# Display.net
KiCad netlist of a schematic drawn in EAGLE
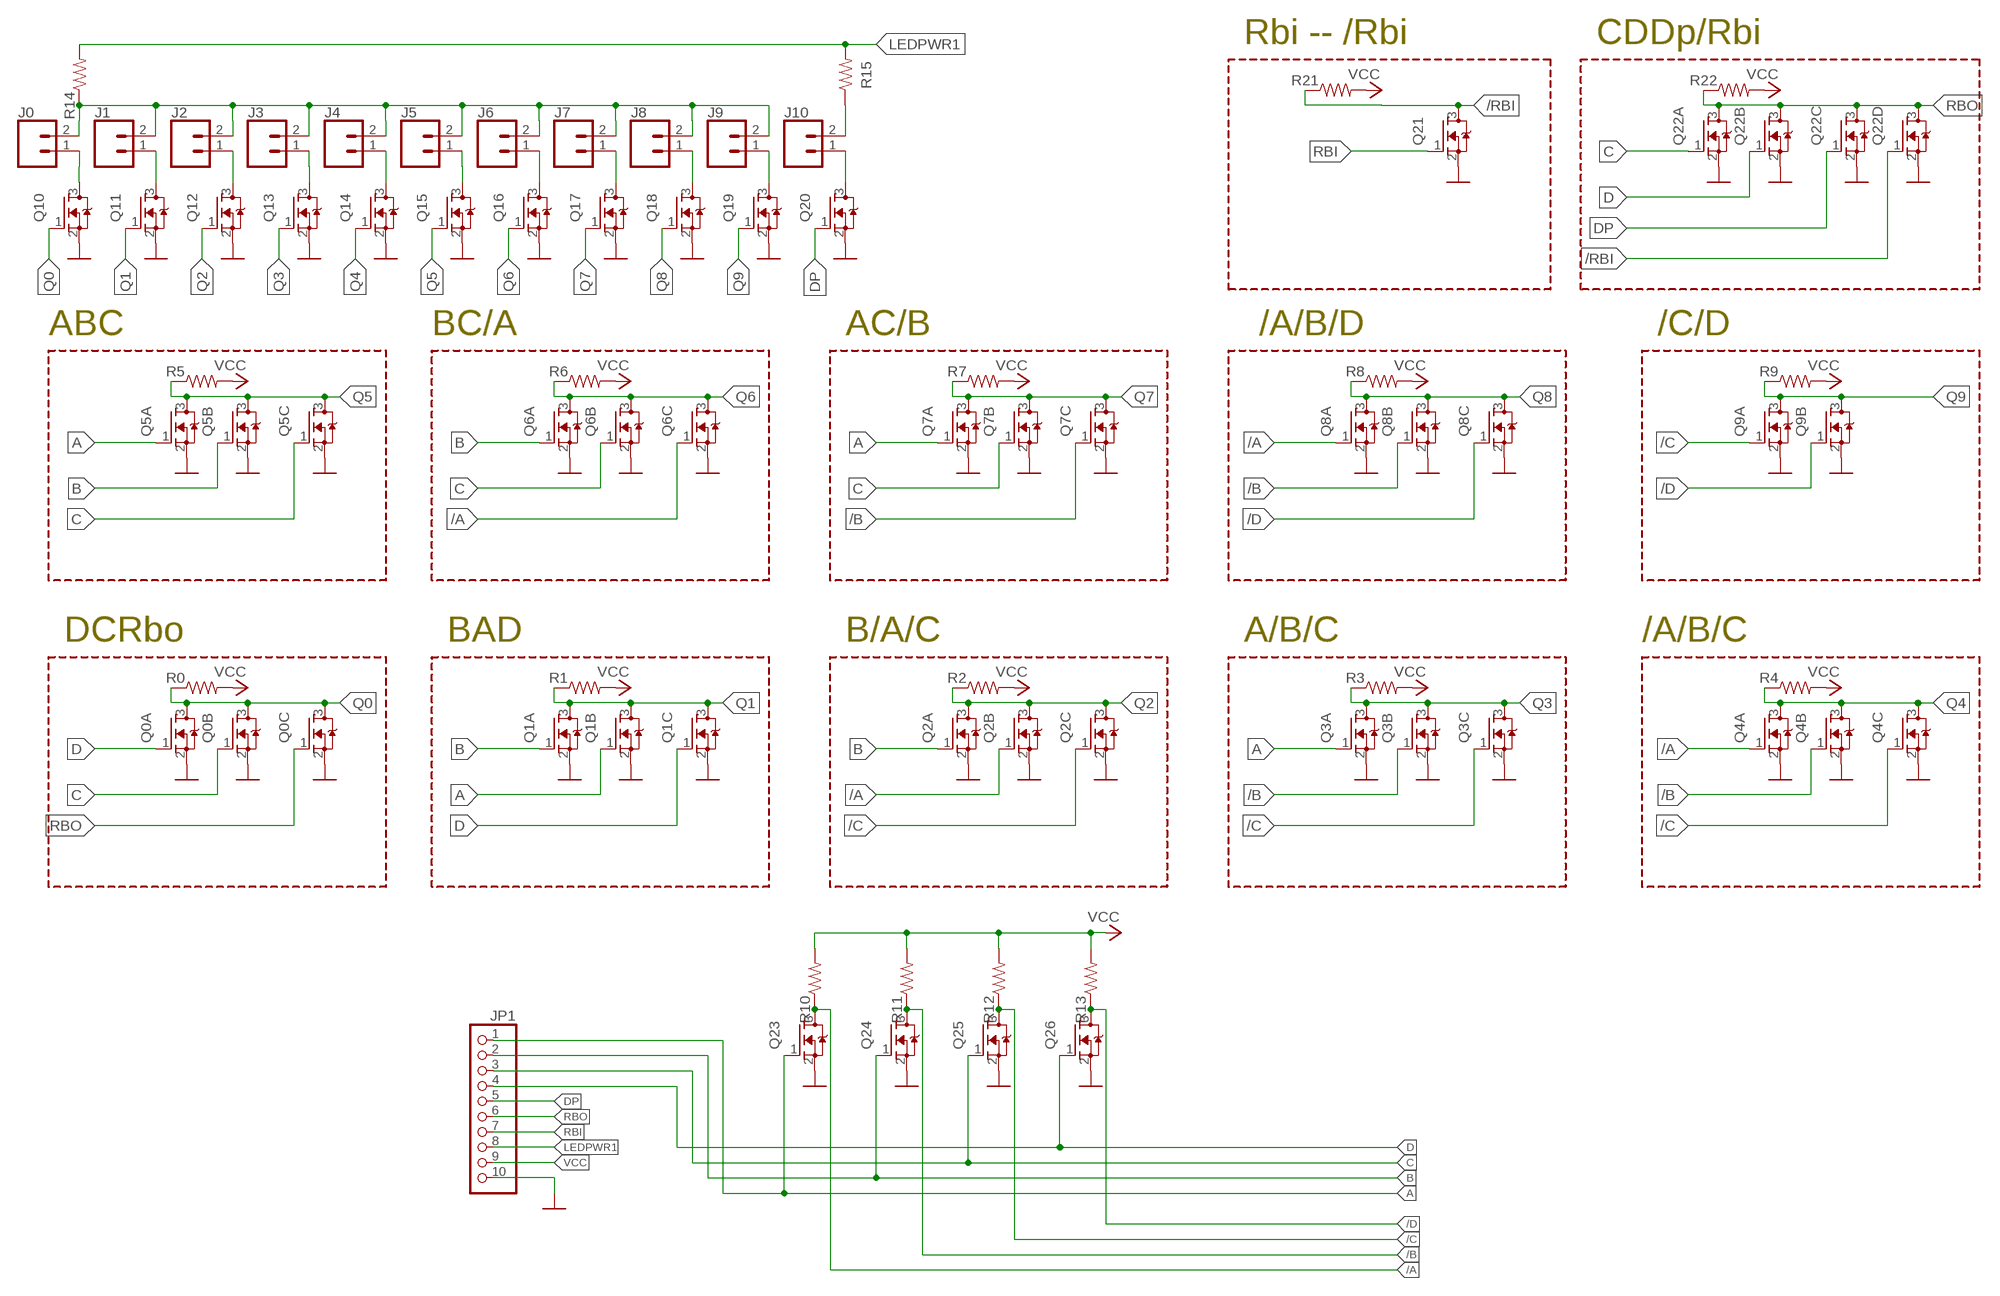
[diagram p0: schematic, sheet 1]

(export (version "E")
  (design (tool "Eeschema 10.0.6"))
  (components
    (comp (ref "J0")
      (value "CONN_02")
      (footprint "eagle-import:1X02")
      (libsource (lib "eagle-import") (part "CONN_02"))
    )
    (comp (ref "J1")
      (value "CONN_02")
      (footprint "eagle-import:1X02")
      (libsource (lib "eagle-import") (part "CONN_02"))
    )
    (comp (ref "J2")
      (value "CONN_02")
      (footprint "eagle-import:1X02")
      (libsource (lib "eagle-import") (part "CONN_02"))
    )
    (comp (ref "J3")
      (value "CONN_02")
      (footprint "eagle-import:1X02")
      (libsource (lib "eagle-import") (part "CONN_02"))
    )
    (comp (ref "J4")
      (value "CONN_02")
      (footprint "eagle-import:1X02")
      (libsource (lib "eagle-import") (part "CONN_02"))
    )
    (comp (ref "J5")
      (value "CONN_02")
      (footprint "eagle-import:1X02")
      (libsource (lib "eagle-import") (part "CONN_02"))
    )
    (comp (ref "J6")
      (value "CONN_02")
      (footprint "eagle-import:1X02")
      (libsource (lib "eagle-import") (part "CONN_02"))
    )
    (comp (ref "J7")
      (value "CONN_02")
      (footprint "eagle-import:1X02")
      (libsource (lib "eagle-import") (part "CONN_02"))
    )
    (comp (ref "J8")
      (value "CONN_02")
      (footprint "eagle-import:1X02")
      (libsource (lib "eagle-import") (part "CONN_02"))
    )
    (comp (ref "J9")
      (value "CONN_02")
      (footprint "eagle-import:1X02")
      (libsource (lib "eagle-import") (part "CONN_02"))
    )
    (comp (ref "J10")
      (value "CONN_02")
      (footprint "eagle-import:1X02")
      (libsource (lib "eagle-import") (part "CONN_02"))
    )
    (comp (ref "JP1")
      (value "PINHD-1X10/90")
      (footprint "eagle-import:1X10_90")
      (libsource (lib "eagle-import") (part "PINHD-1X10/90"))
    )
    (comp (ref "Q0A")
      (value "310mA/60V/1.6Ω")
      (footprint "eagle-import:SOT23")
      (libsource (lib "eagle-import") (part "NMOSREFLOW"))
    )
    (comp (ref "Q0B")
      (value "310mA/60V/1.6Ω")
      (footprint "eagle-import:SOT23")
      (libsource (lib "eagle-import") (part "NMOSREFLOW"))
    )
    (comp (ref "Q0C")
      (value "310mA/60V/1.6Ω")
      (footprint "eagle-import:SOT23")
      (libsource (lib "eagle-import") (part "NMOSREFLOW"))
    )
    (comp (ref "Q1A")
      (value "310mA/60V/1.6Ω")
      (footprint "eagle-import:SOT23")
      (libsource (lib "eagle-import") (part "NMOSREFLOW"))
    )
    (comp (ref "Q1B")
      (value "310mA/60V/1.6Ω")
      (footprint "eagle-import:SOT23")
      (libsource (lib "eagle-import") (part "NMOSREFLOW"))
    )
    (comp (ref "Q1C")
      (value "310mA/60V/1.6Ω")
      (footprint "eagle-import:SOT23")
      (libsource (lib "eagle-import") (part "NMOSREFLOW"))
    )
    (comp (ref "Q2A")
      (value "310mA/60V/1.6Ω")
      (footprint "eagle-import:SOT23")
      (libsource (lib "eagle-import") (part "NMOSREFLOW"))
    )
    (comp (ref "Q2B")
      (value "310mA/60V/1.6Ω")
      (footprint "eagle-import:SOT23")
      (libsource (lib "eagle-import") (part "NMOSREFLOW"))
    )
    (comp (ref "Q2C")
      (value "310mA/60V/1.6Ω")
      (footprint "eagle-import:SOT23")
      (libsource (lib "eagle-import") (part "NMOSREFLOW"))
    )
    (comp (ref "Q3A")
      (value "310mA/60V/1.6Ω")
      (footprint "eagle-import:SOT23")
      (libsource (lib "eagle-import") (part "NMOSREFLOW"))
    )
    (comp (ref "Q3B")
      (value "310mA/60V/1.6Ω")
      (footprint "eagle-import:SOT23")
      (libsource (lib "eagle-import") (part "NMOSREFLOW"))
    )
    (comp (ref "Q3C")
      (value "310mA/60V/1.6Ω")
      (footprint "eagle-import:SOT23")
      (libsource (lib "eagle-import") (part "NMOSREFLOW"))
    )
    (comp (ref "Q4A")
      (value "310mA/60V/1.6Ω")
      (footprint "eagle-import:SOT23")
      (libsource (lib "eagle-import") (part "NMOSREFLOW"))
    )
    (comp (ref "Q4B")
      (value "310mA/60V/1.6Ω")
      (footprint "eagle-import:SOT23")
      (libsource (lib "eagle-import") (part "NMOSREFLOW"))
    )
    (comp (ref "Q4C")
      (value "310mA/60V/1.6Ω")
      (footprint "eagle-import:SOT23")
      (libsource (lib "eagle-import") (part "NMOSREFLOW"))
    )
    (comp (ref "Q5A")
      (value "310mA/60V/1.6Ω")
      (footprint "eagle-import:SOT23")
      (libsource (lib "eagle-import") (part "NMOSREFLOW"))
    )
    (comp (ref "Q5B")
      (value "310mA/60V/1.6Ω")
      (footprint "eagle-import:SOT23")
      (libsource (lib "eagle-import") (part "NMOSREFLOW"))
    )
    (comp (ref "Q5C")
      (value "310mA/60V/1.6Ω")
      (footprint "eagle-import:SOT23")
      (libsource (lib "eagle-import") (part "NMOSREFLOW"))
    )
    (comp (ref "Q6A")
      (value "310mA/60V/1.6Ω")
      (footprint "eagle-import:SOT23")
      (libsource (lib "eagle-import") (part "NMOSREFLOW"))
    )
    (comp (ref "Q6B")
      (value "310mA/60V/1.6Ω")
      (footprint "eagle-import:SOT23")
      (libsource (lib "eagle-import") (part "NMOSREFLOW"))
    )
    (comp (ref "Q6C")
      (value "310mA/60V/1.6Ω")
      (footprint "eagle-import:SOT23")
      (libsource (lib "eagle-import") (part "NMOSREFLOW"))
    )
    (comp (ref "Q7A")
      (value "310mA/60V/1.6Ω")
      (footprint "eagle-import:SOT23")
      (libsource (lib "eagle-import") (part "NMOSREFLOW"))
    )
    (comp (ref "Q7B")
      (value "310mA/60V/1.6Ω")
      (footprint "eagle-import:SOT23")
      (libsource (lib "eagle-import") (part "NMOSREFLOW"))
    )
    (comp (ref "Q7C")
      (value "310mA/60V/1.6Ω")
      (footprint "eagle-import:SOT23")
      (libsource (lib "eagle-import") (part "NMOSREFLOW"))
    )
    (comp (ref "Q8A")
      (value "310mA/60V/1.6Ω")
      (footprint "eagle-import:SOT23")
      (libsource (lib "eagle-import") (part "NMOSREFLOW"))
    )
    (comp (ref "Q8B")
      (value "310mA/60V/1.6Ω")
      (footprint "eagle-import:SOT23")
      (libsource (lib "eagle-import") (part "NMOSREFLOW"))
    )
    (comp (ref "Q8C")
      (value "310mA/60V/1.6Ω")
      (footprint "eagle-import:SOT23")
      (libsource (lib "eagle-import") (part "NMOSREFLOW"))
    )
    (comp (ref "Q9A")
      (value "310mA/60V/1.6Ω")
      (footprint "eagle-import:SOT23")
      (libsource (lib "eagle-import") (part "NMOSREFLOW"))
    )
    (comp (ref "Q9B")
      (value "310mA/60V/1.6Ω")
      (footprint "eagle-import:SOT23")
      (libsource (lib "eagle-import") (part "NMOSREFLOW"))
    )
    (comp (ref "Q10")
      (value "310mA/60V/1.6Ω")
      (footprint "eagle-import:SOT23")
      (libsource (lib "eagle-import") (part "NMOSREFLOW"))
    )
    (comp (ref "Q11")
      (value "310mA/60V/1.6Ω")
      (footprint "eagle-import:SOT23")
      (libsource (lib "eagle-import") (part "NMOSREFLOW"))
    )
    (comp (ref "Q12")
      (value "310mA/60V/1.6Ω")
      (footprint "eagle-import:SOT23")
      (libsource (lib "eagle-import") (part "NMOSREFLOW"))
    )
    (comp (ref "Q13")
      (value "310mA/60V/1.6Ω")
      (footprint "eagle-import:SOT23")
      (libsource (lib "eagle-import") (part "NMOSREFLOW"))
    )
    (comp (ref "Q14")
      (value "310mA/60V/1.6Ω")
      (footprint "eagle-import:SOT23")
      (libsource (lib "eagle-import") (part "NMOSREFLOW"))
    )
    (comp (ref "Q15")
      (value "310mA/60V/1.6Ω")
      (footprint "eagle-import:SOT23")
      (libsource (lib "eagle-import") (part "NMOSREFLOW"))
    )
    (comp (ref "Q16")
      (value "310mA/60V/1.6Ω")
      (footprint "eagle-import:SOT23")
      (libsource (lib "eagle-import") (part "NMOSREFLOW"))
    )
    (comp (ref "Q17")
      (value "310mA/60V/1.6Ω")
      (footprint "eagle-import:SOT23")
      (libsource (lib "eagle-import") (part "NMOSREFLOW"))
    )
    (comp (ref "Q18")
      (value "310mA/60V/1.6Ω")
      (footprint "eagle-import:SOT23")
      (libsource (lib "eagle-import") (part "NMOSREFLOW"))
    )
    (comp (ref "Q19")
      (value "310mA/60V/1.6Ω")
      (footprint "eagle-import:SOT23")
      (libsource (lib "eagle-import") (part "NMOSREFLOW"))
    )
    (comp (ref "Q20")
      (value "310mA/60V/1.6Ω")
      (footprint "eagle-import:SOT23")
      (libsource (lib "eagle-import") (part "NMOSREFLOW"))
    )
    (comp (ref "Q21")
      (value "310mA/60V/1.6Ω")
      (footprint "eagle-import:SOT23")
      (libsource (lib "eagle-import") (part "NMOSREFLOW"))
    )
    (comp (ref "Q22A")
      (value "310mA/60V/1.6Ω")
      (footprint "eagle-import:SOT23")
      (libsource (lib "eagle-import") (part "NMOSREFLOW"))
    )
    (comp (ref "Q22B")
      (value "310mA/60V/1.6Ω")
      (footprint "eagle-import:SOT23")
      (libsource (lib "eagle-import") (part "NMOSREFLOW"))
    )
    (comp (ref "Q22C")
      (value "310mA/60V/1.6Ω")
      (footprint "eagle-import:SOT23")
      (libsource (lib "eagle-import") (part "NMOSREFLOW"))
    )
    (comp (ref "Q22D")
      (value "310mA/60V/1.6Ω")
      (footprint "eagle-import:SOT23")
      (libsource (lib "eagle-import") (part "NMOSREFLOW"))
    )
    (comp (ref "Q23")
      (value "310mA/60V/1.6Ω")
      (footprint "eagle-import:SOT23")
      (libsource (lib "eagle-import") (part "NMOSREFLOW"))
    )
    (comp (ref "Q24")
      (value "310mA/60V/1.6Ω")
      (footprint "eagle-import:SOT23")
      (libsource (lib "eagle-import") (part "NMOSREFLOW"))
    )
    (comp (ref "Q25")
      (value "310mA/60V/1.6Ω")
      (footprint "eagle-import:SOT23")
      (libsource (lib "eagle-import") (part "NMOSREFLOW"))
    )
    (comp (ref "Q26")
      (value "310mA/60V/1.6Ω")
      (footprint "eagle-import:SOT23")
      (libsource (lib "eagle-import") (part "NMOSREFLOW"))
    )
    (comp (ref "R0")
      (value "RESISTOR0805")
      (footprint "eagle-import:0805")
      (libsource (lib "eagle-import") (part "RESISTOR0805"))
    )
    (comp (ref "R1")
      (value "RESISTOR0805")
      (footprint "eagle-import:0805")
      (libsource (lib "eagle-import") (part "RESISTOR0805"))
    )
    (comp (ref "R2")
      (value "RESISTOR0805")
      (footprint "eagle-import:0805")
      (libsource (lib "eagle-import") (part "RESISTOR0805"))
    )
    (comp (ref "R3")
      (value "RESISTOR0805")
      (footprint "eagle-import:0805")
      (libsource (lib "eagle-import") (part "RESISTOR0805"))
    )
    (comp (ref "R4")
      (value "RESISTOR0805")
      (footprint "eagle-import:0805")
      (libsource (lib "eagle-import") (part "RESISTOR0805"))
    )
    (comp (ref "R5")
      (value "RESISTOR0805")
      (footprint "eagle-import:0805")
      (libsource (lib "eagle-import") (part "RESISTOR0805"))
    )
    (comp (ref "R6")
      (value "RESISTOR0805")
      (footprint "eagle-import:0805")
      (libsource (lib "eagle-import") (part "RESISTOR0805"))
    )
    (comp (ref "R7")
      (value "RESISTOR0805")
      (footprint "eagle-import:0805")
      (libsource (lib "eagle-import") (part "RESISTOR0805"))
    )
    (comp (ref "R8")
      (value "RESISTOR0805")
      (footprint "eagle-import:0805")
      (libsource (lib "eagle-import") (part "RESISTOR0805"))
    )
    (comp (ref "R9")
      (value "RESISTOR0805")
      (footprint "eagle-import:0805")
      (libsource (lib "eagle-import") (part "RESISTOR0805"))
    )
    (comp (ref "R10")
      (value "RESISTOR0805")
      (footprint "eagle-import:0805")
      (libsource (lib "eagle-import") (part "RESISTOR0805"))
    )
    (comp (ref "R11")
      (value "RESISTOR0805")
      (footprint "eagle-import:0805")
      (libsource (lib "eagle-import") (part "RESISTOR0805"))
    )
    (comp (ref "R12")
      (value "RESISTOR0805")
      (footprint "eagle-import:0805")
      (libsource (lib "eagle-import") (part "RESISTOR0805"))
    )
    (comp (ref "R13")
      (value "RESISTOR0805")
      (footprint "eagle-import:0805")
      (libsource (lib "eagle-import") (part "RESISTOR0805"))
    )
    (comp (ref "R14")
      (value "RESISTOR0805")
      (footprint "eagle-import:0805")
      (libsource (lib "eagle-import") (part "RESISTOR0805"))
    )
    (comp (ref "R15")
      (value "RESISTOR0805")
      (footprint "eagle-import:0805")
      (libsource (lib "eagle-import") (part "RESISTOR0805"))
    )
    (comp (ref "R21")
      (value "RESISTOR0805")
      (footprint "eagle-import:0805")
      (libsource (lib "eagle-import") (part "RESISTOR0805"))
    )
    (comp (ref "R22")
      (value "RESISTOR0805")
      (footprint "eagle-import:0805")
      (libsource (lib "eagle-import") (part "RESISTOR0805"))
    )
  )
  (nets
    (net (code "1") (name "A") (class "Default")
      (node (ref "JP1") (pin "1") (pinfunction "1_1") (pintype "passive"))
      (node (ref "Q1B") (pin "1") (pinfunction "G_1") (pintype "bidirectional"))
      (node (ref "Q23") (pin "1") (pinfunction "G_1") (pintype "bidirectional"))
      (node (ref "Q3A") (pin "1") (pinfunction "G_1") (pintype "bidirectional"))
      (node (ref "Q5A") (pin "1") (pinfunction "G_1") (pintype "bidirectional"))
      (node (ref "Q7A") (pin "1") (pinfunction "G_1") (pintype "bidirectional"))
    )
    (net (code "2") (name "B") (class "Default")
      (node (ref "JP1") (pin "2") (pinfunction "2_2") (pintype "passive"))
      (node (ref "Q1A") (pin "1") (pinfunction "G_1") (pintype "bidirectional"))
      (node (ref "Q24") (pin "1") (pinfunction "G_1") (pintype "bidirectional"))
      (node (ref "Q2A") (pin "1") (pinfunction "G_1") (pintype "bidirectional"))
      (node (ref "Q5B") (pin "1") (pinfunction "G_1") (pintype "bidirectional"))
      (node (ref "Q6A") (pin "1") (pinfunction "G_1") (pintype "bidirectional"))
    )
    (net (code "3") (name "C") (class "Default")
      (node (ref "JP1") (pin "3") (pinfunction "3_3") (pintype "passive"))
      (node (ref "Q0B") (pin "1") (pinfunction "G_1") (pintype "bidirectional"))
      (node (ref "Q22A") (pin "1") (pinfunction "G_1") (pintype "bidirectional"))
      (node (ref "Q25") (pin "1") (pinfunction "G_1") (pintype "bidirectional"))
      (node (ref "Q5C") (pin "1") (pinfunction "G_1") (pintype "bidirectional"))
      (node (ref "Q6B") (pin "1") (pinfunction "G_1") (pintype "bidirectional"))
      (node (ref "Q7B") (pin "1") (pinfunction "G_1") (pintype "bidirectional"))
    )
    (net (code "4") (name "D") (class "Default")
      (node (ref "JP1") (pin "4") (pinfunction "4_4") (pintype "passive"))
      (node (ref "Q0A") (pin "1") (pinfunction "G_1") (pintype "bidirectional"))
      (node (ref "Q1C") (pin "1") (pinfunction "G_1") (pintype "bidirectional"))
      (node (ref "Q22B") (pin "1") (pinfunction "G_1") (pintype "bidirectional"))
      (node (ref "Q26") (pin "1") (pinfunction "G_1") (pintype "bidirectional"))
    )
    (net (code "5") (name "DP") (class "Default")
      (node (ref "JP1") (pin "5") (pinfunction "5_5") (pintype "passive"))
      (node (ref "Q20") (pin "1") (pinfunction "G_1") (pintype "bidirectional"))
      (node (ref "Q22C") (pin "1") (pinfunction "G_1") (pintype "bidirectional"))
    )
    (net (code "6") (name "GND") (class "Default")
      (node (ref "JP1") (pin "10") (pinfunction "10_10") (pintype "passive"))
      (node (ref "Q0A") (pin "2") (pinfunction "S_2") (pintype "bidirectional"))
      (node (ref "Q0B") (pin "2") (pinfunction "S_2") (pintype "bidirectional"))
      (node (ref "Q0C") (pin "2") (pinfunction "S_2") (pintype "bidirectional"))
      (node (ref "Q10") (pin "2") (pinfunction "S_2") (pintype "bidirectional"))
      (node (ref "Q11") (pin "2") (pinfunction "S_2") (pintype "bidirectional"))
      (node (ref "Q12") (pin "2") (pinfunction "S_2") (pintype "bidirectional"))
      (node (ref "Q13") (pin "2") (pinfunction "S_2") (pintype "bidirectional"))
      (node (ref "Q14") (pin "2") (pinfunction "S_2") (pintype "bidirectional"))
      (node (ref "Q15") (pin "2") (pinfunction "S_2") (pintype "bidirectional"))
      (node (ref "Q16") (pin "2") (pinfunction "S_2") (pintype "bidirectional"))
      (node (ref "Q17") (pin "2") (pinfunction "S_2") (pintype "bidirectional"))
      (node (ref "Q18") (pin "2") (pinfunction "S_2") (pintype "bidirectional"))
      (node (ref "Q19") (pin "2") (pinfunction "S_2") (pintype "bidirectional"))
      (node (ref "Q1A") (pin "2") (pinfunction "S_2") (pintype "bidirectional"))
      (node (ref "Q1B") (pin "2") (pinfunction "S_2") (pintype "bidirectional"))
      (node (ref "Q1C") (pin "2") (pinfunction "S_2") (pintype "bidirectional"))
      (node (ref "Q20") (pin "2") (pinfunction "S_2") (pintype "bidirectional"))
      (node (ref "Q21") (pin "2") (pinfunction "S_2") (pintype "bidirectional"))
      (node (ref "Q22A") (pin "2") (pinfunction "S_2") (pintype "bidirectional"))
      (node (ref "Q22B") (pin "2") (pinfunction "S_2") (pintype "bidirectional"))
      (node (ref "Q22C") (pin "2") (pinfunction "S_2") (pintype "bidirectional"))
      (node (ref "Q22D") (pin "2") (pinfunction "S_2") (pintype "bidirectional"))
      (node (ref "Q23") (pin "2") (pinfunction "S_2") (pintype "bidirectional"))
      (node (ref "Q24") (pin "2") (pinfunction "S_2") (pintype "bidirectional"))
      (node (ref "Q25") (pin "2") (pinfunction "S_2") (pintype "bidirectional"))
      (node (ref "Q26") (pin "2") (pinfunction "S_2") (pintype "bidirectional"))
      (node (ref "Q2A") (pin "2") (pinfunction "S_2") (pintype "bidirectional"))
      (node (ref "Q2B") (pin "2") (pinfunction "S_2") (pintype "bidirectional"))
      (node (ref "Q2C") (pin "2") (pinfunction "S_2") (pintype "bidirectional"))
      (node (ref "Q3A") (pin "2") (pinfunction "S_2") (pintype "bidirectional"))
      (node (ref "Q3B") (pin "2") (pinfunction "S_2") (pintype "bidirectional"))
      (node (ref "Q3C") (pin "2") (pinfunction "S_2") (pintype "bidirectional"))
      (node (ref "Q4A") (pin "2") (pinfunction "S_2") (pintype "bidirectional"))
      (node (ref "Q4B") (pin "2") (pinfunction "S_2") (pintype "bidirectional"))
      (node (ref "Q4C") (pin "2") (pinfunction "S_2") (pintype "bidirectional"))
      (node (ref "Q5A") (pin "2") (pinfunction "S_2") (pintype "bidirectional"))
      (node (ref "Q5B") (pin "2") (pinfunction "S_2") (pintype "bidirectional"))
      (node (ref "Q5C") (pin "2") (pinfunction "S_2") (pintype "bidirectional"))
      (node (ref "Q6A") (pin "2") (pinfunction "S_2") (pintype "bidirectional"))
      (node (ref "Q6B") (pin "2") (pinfunction "S_2") (pintype "bidirectional"))
      (node (ref "Q6C") (pin "2") (pinfunction "S_2") (pintype "bidirectional"))
      (node (ref "Q7A") (pin "2") (pinfunction "S_2") (pintype "bidirectional"))
      (node (ref "Q7B") (pin "2") (pinfunction "S_2") (pintype "bidirectional"))
      (node (ref "Q7C") (pin "2") (pinfunction "S_2") (pintype "bidirectional"))
      (node (ref "Q8A") (pin "2") (pinfunction "S_2") (pintype "bidirectional"))
      (node (ref "Q8B") (pin "2") (pinfunction "S_2") (pintype "bidirectional"))
      (node (ref "Q8C") (pin "2") (pinfunction "S_2") (pintype "bidirectional"))
      (node (ref "Q9A") (pin "2") (pinfunction "S_2") (pintype "bidirectional"))
      (node (ref "Q9B") (pin "2") (pinfunction "S_2") (pintype "bidirectional"))
    )
    (net (code "7") (name "LEDPWR1") (class "Default")
      (node (ref "JP1") (pin "8") (pinfunction "8_8") (pintype "passive"))
      (node (ref "R14") (pin "2") (pinfunction "2_2") (pintype "passive"))
      (node (ref "R15") (pin "2") (pinfunction "2_2") (pintype "passive"))
    )
    (net (code "8") (name "Net-(J0-Pad2)") (class "Default")
      (node (ref "J0") (pin "2") (pinfunction "2_2") (pintype "passive"))
      (node (ref "J1") (pin "2") (pinfunction "2_2") (pintype "passive"))
      (node (ref "J2") (pin "2") (pinfunction "2_2") (pintype "passive"))
      (node (ref "J3") (pin "2") (pinfunction "2_2") (pintype "passive"))
      (node (ref "J4") (pin "2") (pinfunction "2_2") (pintype "passive"))
      (node (ref "J5") (pin "2") (pinfunction "2_2") (pintype "passive"))
      (node (ref "J6") (pin "2") (pinfunction "2_2") (pintype "passive"))
      (node (ref "J7") (pin "2") (pinfunction "2_2") (pintype "passive"))
      (node (ref "J8") (pin "2") (pinfunction "2_2") (pintype "passive"))
      (node (ref "J9") (pin "2") (pinfunction "2_2") (pintype "passive"))
      (node (ref "R14") (pin "1") (pinfunction "1_1") (pintype "passive"))
    )
    (net (code "9") (name "Net-(J10-Pad2)") (class "Default")
      (node (ref "J10") (pin "2") (pinfunction "2_2") (pintype "passive"))
      (node (ref "R15") (pin "1") (pinfunction "1_1") (pintype "passive"))
    )
    (net (code "10") (name "Net-(Q10-D)") (class "Default")
      (node (ref "J0") (pin "1") (pinfunction "1_1") (pintype "passive"))
      (node (ref "Q10") (pin "3") (pinfunction "D_3") (pintype "bidirectional"))
    )
    (net (code "11") (name "Net-(Q11-D)") (class "Default")
      (node (ref "J1") (pin "1") (pinfunction "1_1") (pintype "passive"))
      (node (ref "Q11") (pin "3") (pinfunction "D_3") (pintype "bidirectional"))
    )
    (net (code "12") (name "Net-(Q12-D)") (class "Default")
      (node (ref "J2") (pin "1") (pinfunction "1_1") (pintype "passive"))
      (node (ref "Q12") (pin "3") (pinfunction "D_3") (pintype "bidirectional"))
    )
    (net (code "13") (name "Net-(Q13-D)") (class "Default")
      (node (ref "J3") (pin "1") (pinfunction "1_1") (pintype "passive"))
      (node (ref "Q13") (pin "3") (pinfunction "D_3") (pintype "bidirectional"))
    )
    (net (code "14") (name "Net-(Q14-D)") (class "Default")
      (node (ref "J4") (pin "1") (pinfunction "1_1") (pintype "passive"))
      (node (ref "Q14") (pin "3") (pinfunction "D_3") (pintype "bidirectional"))
    )
    (net (code "15") (name "Net-(Q15-D)") (class "Default")
      (node (ref "J5") (pin "1") (pinfunction "1_1") (pintype "passive"))
      (node (ref "Q15") (pin "3") (pinfunction "D_3") (pintype "bidirectional"))
    )
    (net (code "16") (name "Net-(Q16-D)") (class "Default")
      (node (ref "J6") (pin "1") (pinfunction "1_1") (pintype "passive"))
      (node (ref "Q16") (pin "3") (pinfunction "D_3") (pintype "bidirectional"))
    )
    (net (code "17") (name "Net-(Q17-D)") (class "Default")
      (node (ref "J7") (pin "1") (pinfunction "1_1") (pintype "passive"))
      (node (ref "Q17") (pin "3") (pinfunction "D_3") (pintype "bidirectional"))
    )
    (net (code "18") (name "Net-(Q18-D)") (class "Default")
      (node (ref "J8") (pin "1") (pinfunction "1_1") (pintype "passive"))
      (node (ref "Q18") (pin "3") (pinfunction "D_3") (pintype "bidirectional"))
    )
    (net (code "19") (name "Net-(Q19-D)") (class "Default")
      (node (ref "J9") (pin "1") (pinfunction "1_1") (pintype "passive"))
      (node (ref "Q19") (pin "3") (pinfunction "D_3") (pintype "bidirectional"))
    )
    (net (code "20") (name "Net-(Q20-D)") (class "Default")
      (node (ref "J10") (pin "1") (pinfunction "1_1") (pintype "passive"))
      (node (ref "Q20") (pin "3") (pinfunction "D_3") (pintype "bidirectional"))
    )
    (net (code "21") (name "Q0") (class "Default")
      (node (ref "Q0A") (pin "3") (pinfunction "D_3") (pintype "bidirectional"))
      (node (ref "Q0B") (pin "3") (pinfunction "D_3") (pintype "bidirectional"))
      (node (ref "Q0C") (pin "3") (pinfunction "D_3") (pintype "bidirectional"))
      (node (ref "Q10") (pin "1") (pinfunction "G_1") (pintype "bidirectional"))
      (node (ref "R0") (pin "1") (pinfunction "1_1") (pintype "passive"))
    )
    (net (code "22") (name "Q1") (class "Default")
      (node (ref "Q11") (pin "1") (pinfunction "G_1") (pintype "bidirectional"))
      (node (ref "Q1A") (pin "3") (pinfunction "D_3") (pintype "bidirectional"))
      (node (ref "Q1B") (pin "3") (pinfunction "D_3") (pintype "bidirectional"))
      (node (ref "Q1C") (pin "3") (pinfunction "D_3") (pintype "bidirectional"))
      (node (ref "R1") (pin "1") (pinfunction "1_1") (pintype "passive"))
    )
    (net (code "23") (name "Q2") (class "Default")
      (node (ref "Q12") (pin "1") (pinfunction "G_1") (pintype "bidirectional"))
      (node (ref "Q2A") (pin "3") (pinfunction "D_3") (pintype "bidirectional"))
      (node (ref "Q2B") (pin "3") (pinfunction "D_3") (pintype "bidirectional"))
      (node (ref "Q2C") (pin "3") (pinfunction "D_3") (pintype "bidirectional"))
      (node (ref "R2") (pin "1") (pinfunction "1_1") (pintype "passive"))
    )
    (net (code "24") (name "Q3") (class "Default")
      (node (ref "Q13") (pin "1") (pinfunction "G_1") (pintype "bidirectional"))
      (node (ref "Q3A") (pin "3") (pinfunction "D_3") (pintype "bidirectional"))
      (node (ref "Q3B") (pin "3") (pinfunction "D_3") (pintype "bidirectional"))
      (node (ref "Q3C") (pin "3") (pinfunction "D_3") (pintype "bidirectional"))
      (node (ref "R3") (pin "1") (pinfunction "1_1") (pintype "passive"))
    )
    (net (code "25") (name "Q4") (class "Default")
      (node (ref "Q14") (pin "1") (pinfunction "G_1") (pintype "bidirectional"))
      (node (ref "Q4A") (pin "3") (pinfunction "D_3") (pintype "bidirectional"))
      (node (ref "Q4B") (pin "3") (pinfunction "D_3") (pintype "bidirectional"))
      (node (ref "Q4C") (pin "3") (pinfunction "D_3") (pintype "bidirectional"))
      (node (ref "R4") (pin "1") (pinfunction "1_1") (pintype "passive"))
    )
    (net (code "26") (name "Q5") (class "Default")
      (node (ref "Q15") (pin "1") (pinfunction "G_1") (pintype "bidirectional"))
      (node (ref "Q5A") (pin "3") (pinfunction "D_3") (pintype "bidirectional"))
      (node (ref "Q5B") (pin "3") (pinfunction "D_3") (pintype "bidirectional"))
      (node (ref "Q5C") (pin "3") (pinfunction "D_3") (pintype "bidirectional"))
      (node (ref "R5") (pin "1") (pinfunction "1_1") (pintype "passive"))
    )
    (net (code "27") (name "Q6") (class "Default")
      (node (ref "Q16") (pin "1") (pinfunction "G_1") (pintype "bidirectional"))
      (node (ref "Q6A") (pin "3") (pinfunction "D_3") (pintype "bidirectional"))
      (node (ref "Q6B") (pin "3") (pinfunction "D_3") (pintype "bidirectional"))
      (node (ref "Q6C") (pin "3") (pinfunction "D_3") (pintype "bidirectional"))
      (node (ref "R6") (pin "1") (pinfunction "1_1") (pintype "passive"))
    )
    (net (code "28") (name "Q7") (class "Default")
      (node (ref "Q17") (pin "1") (pinfunction "G_1") (pintype "bidirectional"))
      (node (ref "Q7A") (pin "3") (pinfunction "D_3") (pintype "bidirectional"))
      (node (ref "Q7B") (pin "3") (pinfunction "D_3") (pintype "bidirectional"))
      (node (ref "Q7C") (pin "3") (pinfunction "D_3") (pintype "bidirectional"))
      (node (ref "R7") (pin "1") (pinfunction "1_1") (pintype "passive"))
    )
    (net (code "29") (name "Q8") (class "Default")
      (node (ref "Q18") (pin "1") (pinfunction "G_1") (pintype "bidirectional"))
      (node (ref "Q8A") (pin "3") (pinfunction "D_3") (pintype "bidirectional"))
      (node (ref "Q8B") (pin "3") (pinfunction "D_3") (pintype "bidirectional"))
      (node (ref "Q8C") (pin "3") (pinfunction "D_3") (pintype "bidirectional"))
      (node (ref "R8") (pin "1") (pinfunction "1_1") (pintype "passive"))
    )
    (net (code "30") (name "Q9") (class "Default")
      (node (ref "Q19") (pin "1") (pinfunction "G_1") (pintype "bidirectional"))
      (node (ref "Q9A") (pin "3") (pinfunction "D_3") (pintype "bidirectional"))
      (node (ref "Q9B") (pin "3") (pinfunction "D_3") (pintype "bidirectional"))
      (node (ref "R9") (pin "1") (pinfunction "1_1") (pintype "passive"))
    )
    (net (code "31") (name "RBI") (class "Default")
      (node (ref "JP1") (pin "7") (pinfunction "7_7") (pintype "passive"))
      (node (ref "Q21") (pin "1") (pinfunction "G_1") (pintype "bidirectional"))
    )
    (net (code "32") (name "RBO") (class "Default")
      (node (ref "JP1") (pin "6") (pinfunction "6_6") (pintype "passive"))
      (node (ref "Q0C") (pin "1") (pinfunction "G_1") (pintype "bidirectional"))
      (node (ref "Q22A") (pin "3") (pinfunction "D_3") (pintype "bidirectional"))
      (node (ref "Q22B") (pin "3") (pinfunction "D_3") (pintype "bidirectional"))
      (node (ref "Q22C") (pin "3") (pinfunction "D_3") (pintype "bidirectional"))
      (node (ref "Q22D") (pin "3") (pinfunction "D_3") (pintype "bidirectional"))
      (node (ref "R22") (pin "1") (pinfunction "1_1") (pintype "passive"))
    )
    (net (code "33") (name "VCC") (class "Default")
      (node (ref "JP1") (pin "9") (pinfunction "9_9") (pintype "passive"))
      (node (ref "R0") (pin "2") (pinfunction "2_2") (pintype "passive"))
      (node (ref "R1") (pin "2") (pinfunction "2_2") (pintype "passive"))
      (node (ref "R10") (pin "2") (pinfunction "2_2") (pintype "passive"))
      (node (ref "R11") (pin "2") (pinfunction "2_2") (pintype "passive"))
      (node (ref "R12") (pin "2") (pinfunction "2_2") (pintype "passive"))
      (node (ref "R13") (pin "2") (pinfunction "2_2") (pintype "passive"))
      (node (ref "R2") (pin "2") (pinfunction "2_2") (pintype "passive"))
      (node (ref "R21") (pin "2") (pinfunction "2_2") (pintype "passive"))
      (node (ref "R22") (pin "2") (pinfunction "2_2") (pintype "passive"))
      (node (ref "R3") (pin "2") (pinfunction "2_2") (pintype "passive"))
      (node (ref "R4") (pin "2") (pinfunction "2_2") (pintype "passive"))
      (node (ref "R5") (pin "2") (pinfunction "2_2") (pintype "passive"))
      (node (ref "R6") (pin "2") (pinfunction "2_2") (pintype "passive"))
      (node (ref "R7") (pin "2") (pinfunction "2_2") (pintype "passive"))
      (node (ref "R8") (pin "2") (pinfunction "2_2") (pintype "passive"))
      (node (ref "R9") (pin "2") (pinfunction "2_2") (pintype "passive"))
    )
    (net (code "34") (name "{slash}A") (class "Default")
      (node (ref "Q23") (pin "3") (pinfunction "D_3") (pintype "bidirectional"))
      (node (ref "Q2B") (pin "1") (pinfunction "G_1") (pintype "bidirectional"))
      (node (ref "Q4A") (pin "1") (pinfunction "G_1") (pintype "bidirectional"))
      (node (ref "Q6C") (pin "1") (pinfunction "G_1") (pintype "bidirectional"))
      (node (ref "Q8A") (pin "1") (pinfunction "G_1") (pintype "bidirectional"))
      (node (ref "R10") (pin "1") (pinfunction "1_1") (pintype "passive"))
    )
    (net (code "35") (name "{slash}B") (class "Default")
      (node (ref "Q24") (pin "3") (pinfunction "D_3") (pintype "bidirectional"))
      (node (ref "Q3B") (pin "1") (pinfunction "G_1") (pintype "bidirectional"))
      (node (ref "Q4B") (pin "1") (pinfunction "G_1") (pintype "bidirectional"))
      (node (ref "Q7C") (pin "1") (pinfunction "G_1") (pintype "bidirectional"))
      (node (ref "Q8B") (pin "1") (pinfunction "G_1") (pintype "bidirectional"))
      (node (ref "R11") (pin "1") (pinfunction "1_1") (pintype "passive"))
    )
    (net (code "36") (name "{slash}C") (class "Default")
      (node (ref "Q25") (pin "3") (pinfunction "D_3") (pintype "bidirectional"))
      (node (ref "Q2C") (pin "1") (pinfunction "G_1") (pintype "bidirectional"))
      (node (ref "Q3C") (pin "1") (pinfunction "G_1") (pintype "bidirectional"))
      (node (ref "Q4C") (pin "1") (pinfunction "G_1") (pintype "bidirectional"))
      (node (ref "Q9A") (pin "1") (pinfunction "G_1") (pintype "bidirectional"))
      (node (ref "R12") (pin "1") (pinfunction "1_1") (pintype "passive"))
    )
    (net (code "37") (name "{slash}D") (class "Default")
      (node (ref "Q26") (pin "3") (pinfunction "D_3") (pintype "bidirectional"))
      (node (ref "Q8C") (pin "1") (pinfunction "G_1") (pintype "bidirectional"))
      (node (ref "Q9B") (pin "1") (pinfunction "G_1") (pintype "bidirectional"))
      (node (ref "R13") (pin "1") (pinfunction "1_1") (pintype "passive"))
    )
    (net (code "38") (name "{slash}RBI") (class "Default")
      (node (ref "Q21") (pin "3") (pinfunction "D_3") (pintype "bidirectional"))
      (node (ref "Q22D") (pin "1") (pinfunction "G_1") (pintype "bidirectional"))
      (node (ref "R21") (pin "1") (pinfunction "1_1") (pintype "passive"))
    )
  )
)
